# Gagabiro_supply_maida.net
KiCad netlist of a schematic drawn in Altium Designer
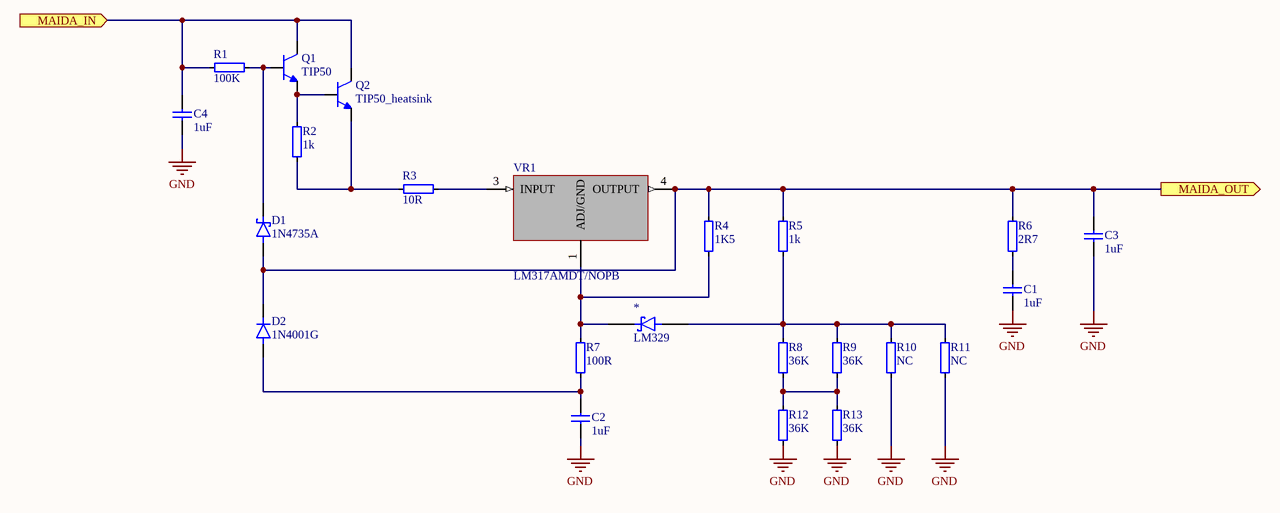
[diagram p0: Gagabiro_supply_maida.SchDoc]

(export (version "E")
  (design (tool "Eeschema 10.0.6"))
  (components
    (comp (ref "*")
      (value "LM329")
      (footprint "TO92127P495H495-3")
      (libsource (lib "Persephone_Integrated_Library") (part "LM329"))
    )
    (comp (ref "C1")
      (value "1uF")
      (footprint "CAP_panassonic_1u_450V")
      (description "Capacitor, Silver Mica")
      (fields (field (name "PART NUMBER") "CMICA_47PF"))
      (libsource (lib "Persephone_Integrated_Library") (part "CAP_POLY_1u"))
    )
    (comp (ref "C2")
      (value "1uF")
      (footprint "CAP_panassonic_1u_450V")
      (description "Capacitor, Silver Mica")
      (fields (field (name "PART NUMBER") "CMICA_47PF"))
      (libsource (lib "Persephone_Integrated_Library") (part "CAP_POLY_1u"))
    )
    (comp (ref "C3")
      (value "1uF")
      (footprint "CAP_panassonic_1u_450V")
      (description "Capacitor, Silver Mica")
      (fields (field (name "PART NUMBER") "CMICA_47PF"))
      (libsource (lib "Persephone_Integrated_Library") (part "CAP_POLY_1u"))
    )
    (comp (ref "C4")
      (value "1uF")
      (footprint "CAP_panassonic_1u_450V")
      (description "Capacitor, Silver Mica")
      (fields (field (name "PART NUMBER") "CMICA_47PF"))
      (libsource (lib "Persephone_Integrated_Library") (part "CAP_POLY_1u"))
    )
    (comp (ref "D1")
      (value "1N4735A")
      (footprint "DIOAD1036W78L463D272")
      (description "Zener Diode 6.2V 1W Â±5% Through Hole DO-204AL (DO-41)")
      (fields (field (name "MF") "ON Semiconductor"))
      (libsource (lib "Persephone_Integrated_Library") (part "1N4735A"))
    )
    (comp (ref "D2")
      (value "1N4001G")
      (footprint "DIOAD1036W78L470D235")
      (description "1A, 50V, Standard Recovery Rectifier")
      (fields (field (name "MF") "Taiwan Semiconductor"))
      (libsource (lib "Persephone_Integrated_Library") (part "1N4001G"))
    )
    (comp (ref "Q1")
      (value "TIP50")
      (footprint "TO254P1009X445X1985-3")
      (description "Bipolar (BJT) Transistor NPN 400 V 1 A 10MHz 2 W Through Hole TO-220-3")
      (fields (field (name "MF") "ON Semiconductor"))
      (libsource (lib "Persephone_Integrated_Library") (part "TIP50"))
    )
    (comp (ref "Q2")
      (value "TIP50_heatsink")
      (footprint "TO254P1009X445X1985-3_heatsink")
      (description "Bipolar (BJT) Transistor NPN 400 V 1 A 10MHz 2 W Through Hole TO-220-3")
      (fields (field (name "MF") "ON Semiconductor") (field (name "MP") "TIP50"))
      (libsource (lib "Persephone_Integrated_Library") (part "TIP50_heatsink"))
    )
    (comp (ref "R1")
      (value "100K")
      (footprint "RES_2W_vertical")
      (description "Resistor, 2W")
      (fields (field (name "PART NUMBER") "R2W") (field (name "AUTHOR") "colombari"))
      (libsource (lib "Persephone_Integrated_Library") (part "R_2W_vertical_100K"))
    )
    (comp (ref "R2")
      (value "1k")
      (footprint "RES_2W_vertical")
      (description "Resistor, 2W")
      (fields (field (name "PART NUMBER") "R2W") (field (name "AUTHOR") "colombari"))
      (libsource (lib "Persephone_Integrated_Library") (part "R_2W_vertical_1k"))
    )
    (comp (ref "R3")
      (value "10R")
      (footprint "RES_2W_vertical")
      (description "Resistor, 2W")
      (fields (field (name "PART NUMBER") "R2W") (field (name "AUTHOR") "colombari"))
      (libsource (lib "Persephone_Integrated_Library") (part "R_2W_vertical_10R"))
    )
    (comp (ref "R4")
      (value "1K5")
      (footprint "RES_2W_vertical")
      (description "Resistor, 2W")
      (fields (field (name "PART NUMBER") "R2W") (field (name "AUTHOR") "colombari"))
      (libsource (lib "Persephone_Integrated_Library") (part "R_2W_vertical_1K5"))
    )
    (comp (ref "R5")
      (value "1k")
      (footprint "RES_2W_vertical")
      (description "Resistor, 2W")
      (fields (field (name "PART NUMBER") "R2W") (field (name "AUTHOR") "colombari"))
      (libsource (lib "Persephone_Integrated_Library") (part "R_2W_vertical_1k"))
    )
    (comp (ref "R6")
      (value "2R7")
      (footprint "RES_2W_vertical")
      (description "Resistor, 2W")
      (fields (field (name "PART NUMBER") "R2W") (field (name "AUTHOR") "colombari"))
      (libsource (lib "Persephone_Integrated_Library") (part "R_2W_vertical_2R7"))
    )
    (comp (ref "R7")
      (value "100R")
      (footprint "RES_2W_vertical")
      (description "Resistor, 2W")
      (fields (field (name "PART NUMBER") "R2W") (field (name "AUTHOR") "colombari"))
      (libsource (lib "Persephone_Integrated_Library") (part "R_2W_vertical_100R"))
    )
    (comp (ref "R8")
      (value "36K")
      (footprint "RES_2W_vertical")
      (description "Resistor, 2W")
      (fields (field (name "PART NUMBER") "R2W") (field (name "AUTHOR") "colombari"))
      (libsource (lib "Persephone_Integrated_Library") (part "R_2W_vertical_36K"))
    )
    (comp (ref "R9")
      (value "36K")
      (footprint "RES_2W_vertical")
      (description "Resistor, 2W")
      (fields (field (name "PART NUMBER") "R2W") (field (name "AUTHOR") "colombari"))
      (libsource (lib "Persephone_Integrated_Library") (part "R_2W_vertical_36K"))
    )
    (comp (ref "R10")
      (value "NC")
      (footprint "RES_2W_vertical")
      (description "Resistor, 2W")
      (fields (field (name "PART NUMBER") "R2W") (field (name "AUTHOR") "colombari"))
      (libsource (lib "Persephone_Integrated_Library") (part "R_2W_vertical_NC"))
    )
    (comp (ref "R11")
      (value "NC")
      (footprint "RES_2W_vertical")
      (description "Resistor, 2W")
      (fields (field (name "PART NUMBER") "R2W") (field (name "AUTHOR") "colombari"))
      (libsource (lib "Persephone_Integrated_Library") (part "R_2W_vertical_NC"))
    )
    (comp (ref "R12")
      (value "36K")
      (footprint "RES_2W_vertical")
      (description "Resistor, 2W")
      (fields (field (name "PART NUMBER") "R2W") (field (name "AUTHOR") "colombari"))
      (libsource (lib "Persephone_Integrated_Library") (part "R_2W_vertical_36K"))
    )
    (comp (ref "R13")
      (value "36K")
      (footprint "RES_2W_vertical")
      (description "Resistor, 2W")
      (fields (field (name "PART NUMBER") "R2W") (field (name "AUTHOR") "colombari"))
      (libsource (lib "Persephone_Integrated_Library") (part "R_2W_vertical_36K"))
    )
    (comp (ref "VR1")
      (value "LM317AMDT/NOPB")
      (footprint "TO228P991X255-3N")
      (libsource (lib "Persephone_Integrated_Library") (part "LM317AMDT/NOPB"))
    )
  )
  (nets
    (net (code "1") (name "/MAIDA_IN") (class "Default")
      (node (ref "C4") (pin "2") (pinfunction "2_2") (pintype "passive"))
      (node (ref "Q1") (pin "2") (pinfunction "C_2") (pintype "passive"))
      (node (ref "Q2") (pin "2") (pinfunction "C_2") (pintype "passive"))
      (node (ref "R1") (pin "1") (pinfunction "1_1") (pintype "passive"))
    )
    (net (code "2") (name "/MAIDA_OUT") (class "Default")
      (node (ref "C3") (pin "2") (pinfunction "2_2") (pintype "passive"))
      (node (ref "D1") (pin "2") (pinfunction "A_2") (pintype "passive"))
      (node (ref "D2") (pin "C") (pinfunction "K_C") (pintype "passive"))
      (node (ref "R4") (pin "2") (pinfunction "2_2") (pintype "passive"))
      (node (ref "R5") (pin "2") (pinfunction "2_2") (pintype "passive"))
      (node (ref "R6") (pin "2") (pinfunction "2_2") (pintype "passive"))
      (node (ref "VR1") (pin "4") (pinfunction "OUTPUT_4") (pintype "output"))
    )
    (net (code "3") (name "GND") (class "Default")
      (node (ref "C1") (pin "1") (pinfunction "1_1") (pintype "passive"))
      (node (ref "C2") (pin "1") (pinfunction "1_1") (pintype "passive"))
      (node (ref "C3") (pin "1") (pinfunction "1_1") (pintype "passive"))
      (node (ref "C4") (pin "1") (pinfunction "1_1") (pintype "passive"))
      (node (ref "R10") (pin "1") (pinfunction "1_1") (pintype "passive"))
      (node (ref "R11") (pin "1") (pinfunction "1_1") (pintype "passive"))
      (node (ref "R12") (pin "1") (pinfunction "1_1") (pintype "passive"))
      (node (ref "R13") (pin "1") (pinfunction "1_1") (pintype "passive"))
    )
    (net (code "4") (name "Net-(*-Pad3)") (class "Default")
      (node (ref "*") (pin "3") (pinfunction "3_3") (pintype "power_in"))
      (node (ref "R10") (pin "2") (pinfunction "2_2") (pintype "passive"))
      (node (ref "R11") (pin "2") (pinfunction "2_2") (pintype "passive"))
      (node (ref "R5") (pin "1") (pinfunction "1_1") (pintype "passive"))
      (node (ref "R8") (pin "2") (pinfunction "2_2") (pintype "passive"))
      (node (ref "R9") (pin "2") (pinfunction "2_2") (pintype "passive"))
    )
    (net (code "5") (name "Net-(C1-Pad2)") (class "Default")
      (node (ref "C1") (pin "2") (pinfunction "2_2") (pintype "passive"))
      (node (ref "R6") (pin "1") (pinfunction "1_1") (pintype "passive"))
    )
    (net (code "6") (name "Net-(C2-Pad2)") (class "Default")
      (node (ref "C2") (pin "2") (pinfunction "2_2") (pintype "passive"))
      (node (ref "D2") (pin "A") (pinfunction "A_A") (pintype "passive"))
      (node (ref "R7") (pin "1") (pinfunction "1_1") (pintype "passive"))
    )
    (net (code "7") (name "Net-(D1-K)") (class "Default")
      (node (ref "D1") (pin "1") (pinfunction "K_1") (pintype "passive"))
      (node (ref "Q1") (pin "1") (pinfunction "B_1") (pintype "passive"))
      (node (ref "R1") (pin "2") (pinfunction "2_2") (pintype "passive"))
    )
    (net (code "8") (name "Net-(Q1-E)") (class "Default")
      (node (ref "Q1") (pin "3") (pinfunction "E_3") (pintype "passive"))
      (node (ref "Q2") (pin "1") (pinfunction "B_1") (pintype "passive"))
      (node (ref "R2") (pin "2") (pinfunction "2_2") (pintype "passive"))
    )
    (net (code "9") (name "Net-(Q2-E)") (class "Default")
      (node (ref "Q2") (pin "3") (pinfunction "E_3") (pintype "passive"))
      (node (ref "R2") (pin "1") (pinfunction "1_1") (pintype "passive"))
      (node (ref "R3") (pin "2") (pinfunction "2_2") (pintype "passive"))
    )
    (net (code "10") (name "Net-(R12-Pad2)") (class "Default")
      (node (ref "R12") (pin "2") (pinfunction "2_2") (pintype "passive"))
      (node (ref "R13") (pin "2") (pinfunction "2_2") (pintype "passive"))
      (node (ref "R8") (pin "1") (pinfunction "1_1") (pintype "passive"))
      (node (ref "R9") (pin "1") (pinfunction "1_1") (pintype "passive"))
    )
    (net (code "11") (name "Net-(VR1-ADJ{slash}GND)") (class "Default")
      (node (ref "*") (pin "2") (pinfunction "2_2") (pintype "power_in"))
      (node (ref "R4") (pin "1") (pinfunction "1_1") (pintype "passive"))
      (node (ref "R7") (pin "2") (pinfunction "2_2") (pintype "passive"))
      (node (ref "VR1") (pin "1") (pinfunction "ADJ/GND_1") (pintype "power_in"))
    )
    (net (code "12") (name "Net-(VR1-INPUT)") (class "Default")
      (node (ref "R3") (pin "1") (pinfunction "1_1") (pintype "passive"))
      (node (ref "VR1") (pin "3") (pinfunction "INPUT_3") (pintype "input"))
    )
  )
)
